# df12-20dp-breakout.net
KiCad netlist of a schematic drawn in EAGLE
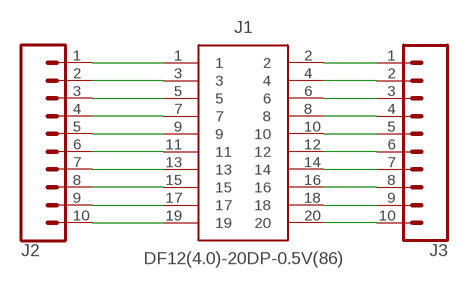
[diagram p0: schematic, sheet 1]

(export (version "E")
  (design (tool "Eeschema 10.0.6"))
  (components
    (comp (ref "J1")
      (value "DF12(4.0)-20DP-0.5V(86)")
      (footprint "eagle-import:DF12(4.0)-20DP")
      (fields (field (name "RS_PART_NUMBER") "6082121P"))
      (libsource (lib "eagle-import") (part "DF12(4.0)-20DP-0.5V(86)"))
    )
    (comp (ref "J2")
      (value "CONN_10LOCK_LONGPADS")
      (footprint "eagle-import:1X10_LOCK_LONGPADS")
      (libsource (lib "eagle-import") (part "CONN_10LOCK_LONGPADS"))
    )
    (comp (ref "J3")
      (value "CONN_10LOCK_LONGPADS")
      (footprint "eagle-import:1X10_LOCK_LONGPADS")
      (libsource (lib "eagle-import") (part "CONN_10LOCK_LONGPADS"))
    )
  )
  (nets
    (net (code "1") (name "Net-(J1-Pad1)") (class "Default")
      (node (ref "J1") (pin "1") (pinfunction "1_1") (pintype "passive"))
      (node (ref "J2") (pin "1") (pinfunction "1_1") (pintype "passive"))
    )
    (net (code "2") (name "Net-(J1-Pad2)") (class "Default")
      (node (ref "J1") (pin "2") (pinfunction "2_2") (pintype "passive"))
      (node (ref "J3") (pin "1") (pinfunction "1_1") (pintype "passive"))
    )
    (net (code "3") (name "Net-(J1-Pad3)") (class "Default")
      (node (ref "J1") (pin "3") (pinfunction "3_3") (pintype "passive"))
      (node (ref "J2") (pin "2") (pinfunction "2_2") (pintype "passive"))
    )
    (net (code "4") (name "Net-(J1-Pad4)") (class "Default")
      (node (ref "J1") (pin "4") (pinfunction "4_4") (pintype "passive"))
      (node (ref "J3") (pin "2") (pinfunction "2_2") (pintype "passive"))
    )
    (net (code "5") (name "Net-(J1-Pad5)") (class "Default")
      (node (ref "J1") (pin "5") (pinfunction "5_5") (pintype "passive"))
      (node (ref "J2") (pin "3") (pinfunction "3_3") (pintype "passive"))
    )
    (net (code "6") (name "Net-(J1-Pad6)") (class "Default")
      (node (ref "J1") (pin "6") (pinfunction "6_6") (pintype "passive"))
      (node (ref "J3") (pin "3") (pinfunction "3_3") (pintype "passive"))
    )
    (net (code "7") (name "Net-(J1-Pad7)") (class "Default")
      (node (ref "J1") (pin "7") (pinfunction "7_7") (pintype "passive"))
      (node (ref "J2") (pin "4") (pinfunction "4_4") (pintype "passive"))
    )
    (net (code "8") (name "Net-(J1-Pad8)") (class "Default")
      (node (ref "J1") (pin "8") (pinfunction "8_8") (pintype "passive"))
      (node (ref "J3") (pin "4") (pinfunction "4_4") (pintype "passive"))
    )
    (net (code "9") (name "Net-(J1-Pad9)") (class "Default")
      (node (ref "J1") (pin "9") (pinfunction "9_9") (pintype "passive"))
      (node (ref "J2") (pin "5") (pinfunction "5_5") (pintype "passive"))
    )
    (net (code "10") (name "Net-(J1-Pad10)") (class "Default")
      (node (ref "J1") (pin "10") (pinfunction "10_10") (pintype "passive"))
      (node (ref "J3") (pin "5") (pinfunction "5_5") (pintype "passive"))
    )
    (net (code "11") (name "Net-(J1-Pad11)") (class "Default")
      (node (ref "J1") (pin "11") (pinfunction "11_11") (pintype "passive"))
      (node (ref "J2") (pin "6") (pinfunction "6_6") (pintype "passive"))
    )
    (net (code "12") (name "Net-(J1-Pad12)") (class "Default")
      (node (ref "J1") (pin "12") (pinfunction "12_12") (pintype "passive"))
      (node (ref "J3") (pin "6") (pinfunction "6_6") (pintype "passive"))
    )
    (net (code "13") (name "Net-(J1-Pad13)") (class "Default")
      (node (ref "J1") (pin "13") (pinfunction "13_13") (pintype "passive"))
      (node (ref "J2") (pin "7") (pinfunction "7_7") (pintype "passive"))
    )
    (net (code "14") (name "Net-(J1-Pad14)") (class "Default")
      (node (ref "J1") (pin "14") (pinfunction "14_14") (pintype "passive"))
      (node (ref "J3") (pin "7") (pinfunction "7_7") (pintype "passive"))
    )
    (net (code "15") (name "Net-(J1-Pad15)") (class "Default")
      (node (ref "J1") (pin "15") (pinfunction "15_15") (pintype "passive"))
      (node (ref "J2") (pin "8") (pinfunction "8_8") (pintype "passive"))
    )
    (net (code "16") (name "Net-(J1-Pad16)") (class "Default")
      (node (ref "J1") (pin "16") (pinfunction "16_16") (pintype "passive"))
      (node (ref "J3") (pin "8") (pinfunction "8_8") (pintype "passive"))
    )
    (net (code "17") (name "Net-(J1-Pad17)") (class "Default")
      (node (ref "J1") (pin "17") (pinfunction "17_17") (pintype "passive"))
      (node (ref "J2") (pin "9") (pinfunction "9_9") (pintype "passive"))
    )
    (net (code "18") (name "Net-(J1-Pad18)") (class "Default")
      (node (ref "J1") (pin "18") (pinfunction "18_18") (pintype "passive"))
      (node (ref "J3") (pin "9") (pinfunction "9_9") (pintype "passive"))
    )
    (net (code "19") (name "Net-(J1-Pad19)") (class "Default")
      (node (ref "J1") (pin "19") (pinfunction "19_19") (pintype "passive"))
      (node (ref "J2") (pin "10") (pinfunction "10_10") (pintype "passive"))
    )
    (net (code "20") (name "Net-(J1-Pad20)") (class "Default")
      (node (ref "J1") (pin "20") (pinfunction "20_20") (pintype "passive"))
      (node (ref "J3") (pin "10") (pinfunction "10_10") (pintype "passive"))
    )
  )
)
